# SWD_PROGRAMMER.net
KiCad netlist of a schematic drawn in EAGLE
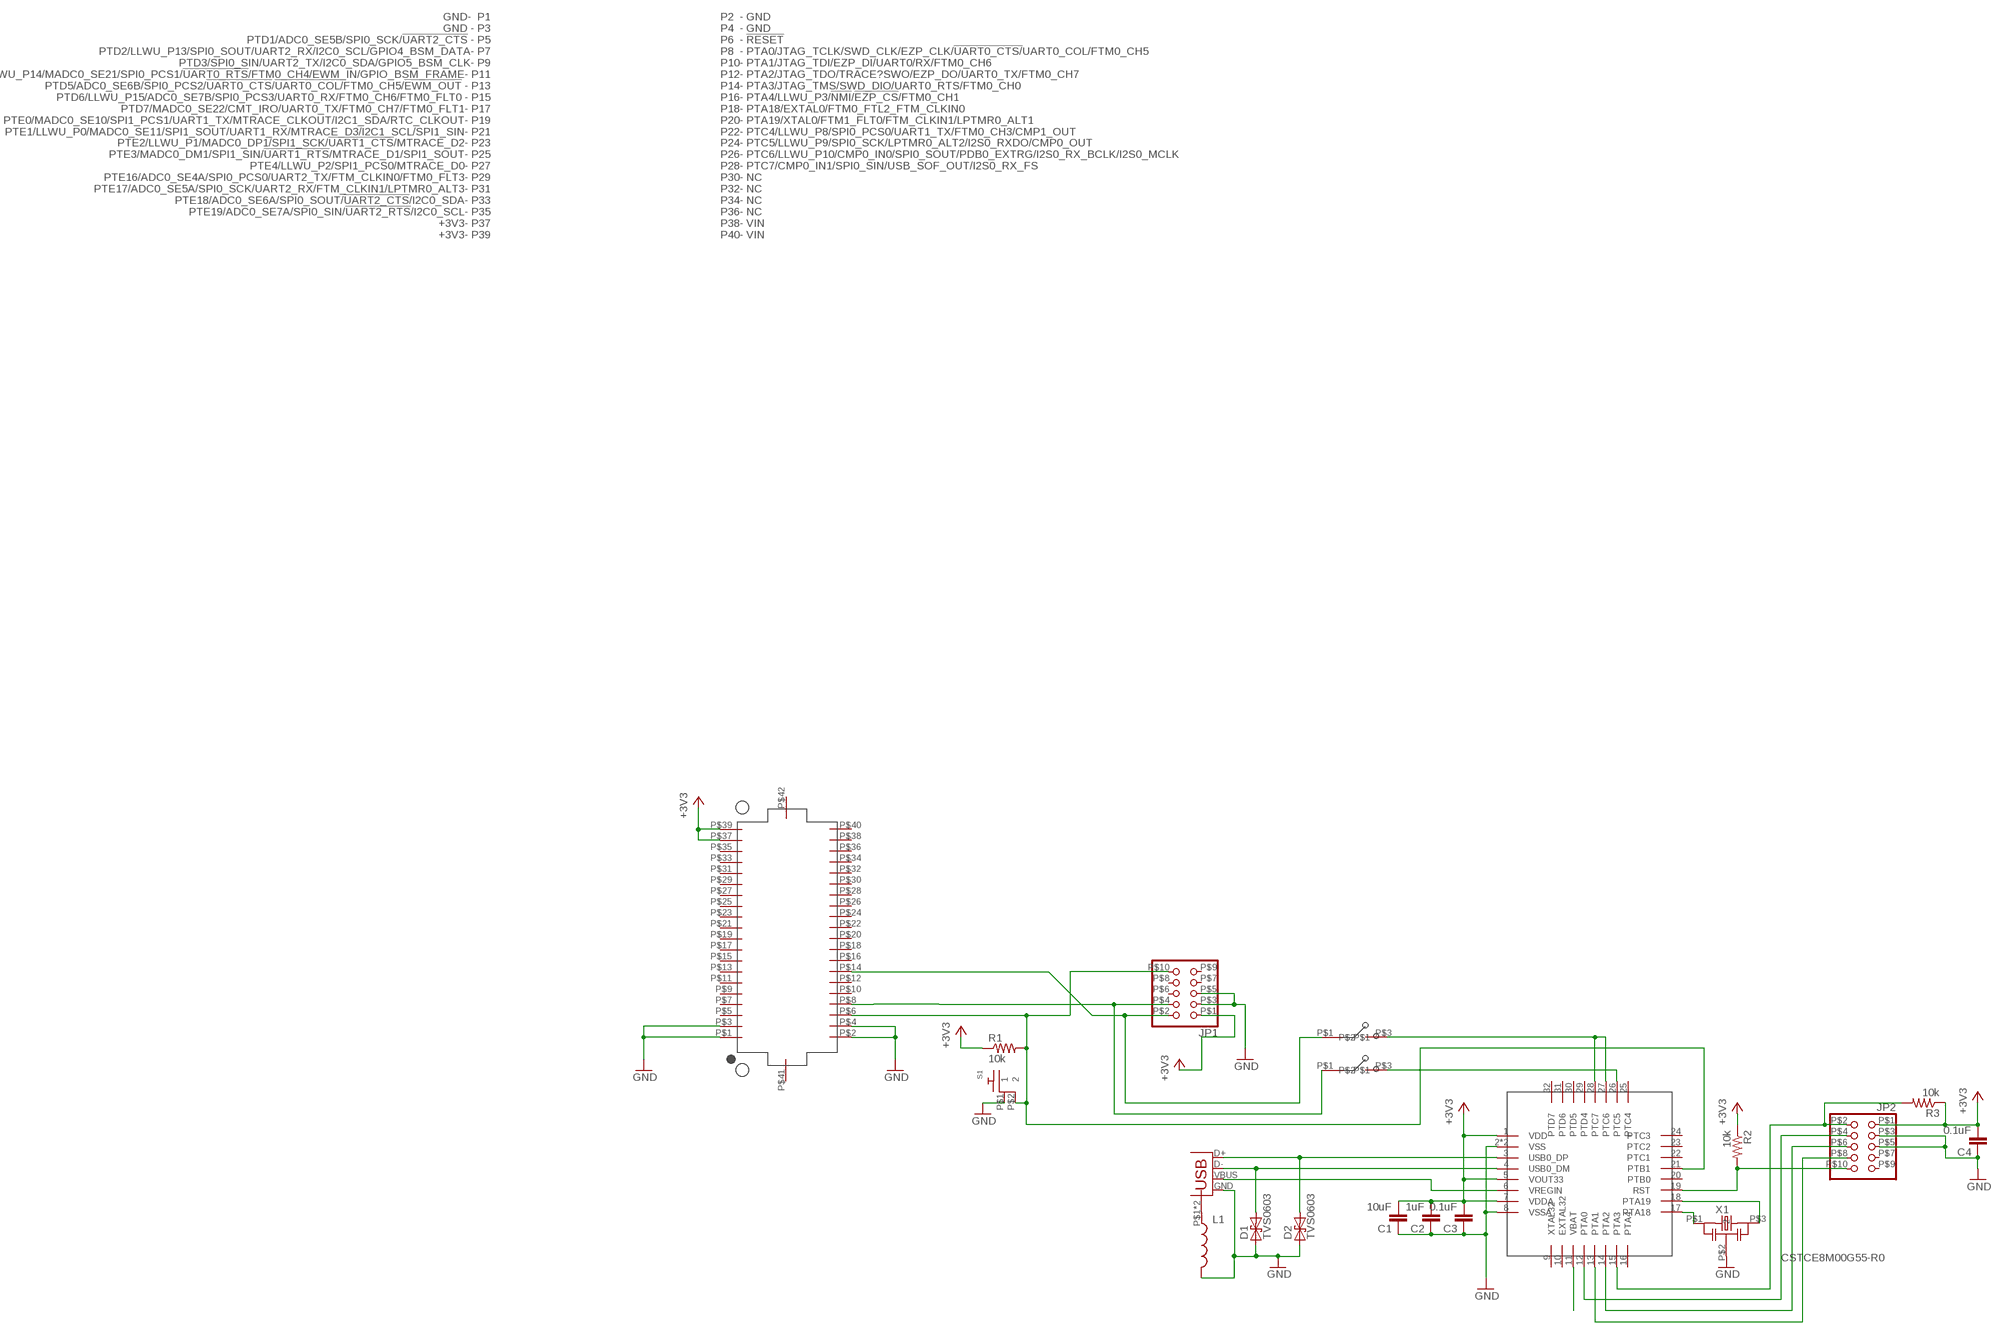
[diagram p0: schematic, sheet 1]

(export (version "E")
  (design (tool "Eeschema 10.0.6"))
  (components
    (comp (ref "C1")
      (value "10uF")
      (footprint "eagle-import:C0805")
      (libsource (lib "eagle-import") (part "RF-C0805"))
    )
    (comp (ref "C2")
      (value "1uF")
      (footprint "eagle-import:C0805")
      (libsource (lib "eagle-import") (part "RF-C0805"))
    )
    (comp (ref "C3")
      (value "0.1uF")
      (footprint "eagle-import:C0805")
      (libsource (lib "eagle-import") (part "RF-C0805"))
    )
    (comp (ref "C4")
      (value "0.1uF")
      (footprint "eagle-import:C0805")
      (libsource (lib "eagle-import") (part "RF-C0805"))
    )
    (comp (ref "D1")
      (value "TVS0603")
      (footprint "eagle-import:0603-RES")
      (libsource (lib "eagle-import") (part "TVS0603"))
    )
    (comp (ref "D2")
      (value "TVS0603")
      (footprint "eagle-import:0603-RES")
      (libsource (lib "eagle-import") (part "TVS0603"))
    )
    (comp (ref "J1")
      (value "USB_B")
      (footprint "eagle-import:USB-B-PTH-VERTICAL")
      (libsource (lib "eagle-import") (part "USB_B"))
    )
    (comp (ref "JP1")
      (value "PINHD-2X5SMALL")
      (footprint "eagle-import:2X5HDR")
      (libsource (lib "eagle-import") (part "PINHD-2X5SMALL"))
    )
    (comp (ref "JP2")
      (value "PINHD-2X5SMALL")
      (footprint "eagle-import:2X5HDR")
      (libsource (lib "eagle-import") (part "PINHD-2X5SMALL"))
    )
    (comp (ref "L1")
      (value "INDUCTOR0603")
      (footprint "eagle-import:0603")
      (libsource (lib "eagle-import") (part "INDUCTOR0603"))
    )
    (comp (ref "R1")
      (value "10k")
      (footprint "eagle-import:RF-C0805")
      (libsource (lib "eagle-import") (part "RF-R0805"))
    )
    (comp (ref "R2")
      (value "10k")
      (footprint "eagle-import:RF-C0805")
      (libsource (lib "eagle-import") (part "RF-R0805"))
    )
    (comp (ref "R3")
      (value "10k")
      (footprint "eagle-import:RF-C0805")
      (libsource (lib "eagle-import") (part "RF-R0805"))
    )
    (comp (ref "S1")
      (value "RA_BUTTON")
      (footprint "eagle-import:RA_BUTTON")
      (libsource (lib "eagle-import") (part "RA_BUTTON"))
    )
    (comp (ref "SW1")
      (value "CJS")
      (footprint "eagle-import:CJS")
      (libsource (lib "eagle-import") (part "CJS"))
    )
    (comp (ref "SW2")
      (value "CJS")
      (footprint "eagle-import:CJS")
      (libsource (lib "eagle-import") (part "CJS"))
    )
    (comp (ref "U1")
      (value "KW2_CPU_OFFSET")
      (footprint "eagle-import:BRAIN_OFFSET")
      (libsource (lib "eagle-import") (part "KW2_CPU_OFFSET"))
    )
    (comp (ref "U2")
      (value "KL20PAD")
      (footprint "eagle-import:QFN-32")
      (libsource (lib "eagle-import") (part "KL20PAD"))
    )
    (comp (ref "X1")
      (value "CSTCE8M00G55-R0")
      (footprint "eagle-import:CSTCE_G_A")
      (libsource (lib "eagle-import") (part "CSTCE8M00G55-R0"))
    )
  )
  (nets
    (net (code "1") (name "+3V3") (class "Default")
      (node (ref "C1") (pin "2") (pinfunction "2_2") (pintype "passive"))
      (node (ref "C2") (pin "2") (pinfunction "2_2") (pintype "passive"))
      (node (ref "C3") (pin "2") (pinfunction "2_2") (pintype "passive"))
      (node (ref "C4") (pin "2") (pinfunction "2_2") (pintype "passive"))
      (node (ref "JP1") (pin "P$1") (pinfunction "1_P$1") (pintype "passive"))
      (node (ref "JP2") (pin "P$1") (pinfunction "1_P$1") (pintype "passive"))
      (node (ref "R1") (pin "1") (pinfunction "1_1") (pintype "passive"))
      (node (ref "R2") (pin "1") (pinfunction "1_1") (pintype "passive"))
      (node (ref "R3") (pin "1") (pinfunction "1_1") (pintype "passive"))
      (node (ref "U1") (pin "P$37") (pinfunction "+3V3_P$37") (pintype "bidirectional"))
      (node (ref "U1") (pin "P$39") (pinfunction "+3V3_P$39") (pintype "bidirectional"))
      (node (ref "U2") (pin "1") (pinfunction "VDD_1") (pintype "bidirectional"))
      (node (ref "U2") (pin "5") (pinfunction "VOUT33_5") (pintype "bidirectional"))
      (node (ref "U2") (pin "7") (pinfunction "VDDA_7") (pintype "bidirectional"))
    )
    (net (code "2") (name "GND") (class "Default")
      (node (ref "C1") (pin "1") (pinfunction "1_1") (pintype "passive"))
      (node (ref "C2") (pin "1") (pinfunction "1_1") (pintype "passive"))
      (node (ref "C3") (pin "1") (pinfunction "1_1") (pintype "passive"))
      (node (ref "C4") (pin "1") (pinfunction "1_1") (pintype "passive"))
      (node (ref "D1") (pin "1") (pinfunction "1_1") (pintype "passive"))
      (node (ref "D2") (pin "1") (pinfunction "1_1") (pintype "passive"))
      (node (ref "J1") (pin "GND") (pinfunction "GND_GND") (pintype "bidirectional"))
      (node (ref "JP1") (pin "P$3") (pinfunction "3_P$3") (pintype "passive"))
      (node (ref "JP1") (pin "P$5") (pinfunction "5_P$5") (pintype "passive"))
      (node (ref "JP2") (pin "P$3") (pinfunction "3_P$3") (pintype "passive"))
      (node (ref "JP2") (pin "P$5") (pinfunction "5_P$5") (pintype "passive"))
      (node (ref "L1") (pin "2") (pinfunction "2_2") (pintype "passive"))
      (node (ref "S1") (pin "P$1") (pinfunction "1_P$1") (pintype "input"))
      (node (ref "U1") (pin "P$1") (pinfunction "GND_P$1") (pintype "bidirectional"))
      (node (ref "U1") (pin "P$2") (pinfunction "GND_P$2") (pintype "bidirectional"))
      (node (ref "U1") (pin "P$3") (pinfunction "GND_P$3") (pintype "bidirectional"))
      (node (ref "U1") (pin "P$4") (pinfunction "GND_P$4") (pintype "bidirectional"))
      (node (ref "U2") (pin "2") (pinfunction "VSS_2") (pintype "bidirectional"))
      (node (ref "U2") (pin "8") (pinfunction "VSSA_8") (pintype "bidirectional"))
      (node (ref "U2") (pin "EP") (pinfunction "VSS_EP") (pintype "bidirectional"))
      (node (ref "X1") (pin "P$2") (pinfunction "2_P$2") (pintype "passive"))
    )
    (net (code "3") (name "Net-(J1-SHIELD-PadP$1)") (class "Default")
      (node (ref "J1") (pin "P$1") (pinfunction "SHIELD_P$1") (pintype "bidirectional"))
      (node (ref "J1") (pin "P$2") (pinfunction "SHIELD_P$2") (pintype "bidirectional"))
      (node (ref "L1") (pin "1") (pinfunction "1_1") (pintype "passive"))
    )
    (net (code "4") (name "Net-(JP1-2)") (class "Default")
      (node (ref "JP1") (pin "P$2") (pinfunction "2_P$2") (pintype "passive"))
      (node (ref "SW1") (pin "P$1") (pinfunction "P$1_P$1") (pintype "bidirectional"))
      (node (ref "U1") (pin "P$14") (pinfunction "PTA3/JTAG_TMS/SWD_DIO/UART0_RTS/FTM0_CH0_P$14") (pintype "bidirectional"))
    )
    (net (code "5") (name "Net-(JP1-4)") (class "Default")
      (node (ref "JP1") (pin "P$4") (pinfunction "4_P$4") (pintype "passive"))
      (node (ref "SW2") (pin "P$1") (pinfunction "P$1_P$1") (pintype "bidirectional"))
      (node (ref "U1") (pin "P$8") (pinfunction "PTA0/JTAG_TCLK/SWD_CLK/EZP_CLK/~{UART0_CTS/}UART0_COL/FTM0_CH5_P$8") (pintype "bidirectional"))
    )
    (net (code "6") (name "Net-(JP1-10)") (class "Default")
      (node (ref "JP1") (pin "P$10") (pinfunction "10_P$10") (pintype "passive"))
      (node (ref "R1") (pin "2") (pinfunction "2_2") (pintype "passive"))
      (node (ref "S1") (pin "P$2") (pinfunction "2_P$2") (pintype "input"))
      (node (ref "U1") (pin "P$6") (pinfunction "~{RESET}_P$6") (pintype "bidirectional"))
      (node (ref "U2") (pin "21") (pinfunction "PTB1_21") (pintype "bidirectional"))
    )
    (net (code "7") (name "Net-(JP2-2)") (class "Default")
      (node (ref "JP2") (pin "P$2") (pinfunction "2_P$2") (pintype "passive"))
      (node (ref "R3") (pin "2") (pinfunction "2_2") (pintype "passive"))
      (node (ref "U2") (pin "15") (pinfunction "PTA3_15") (pintype "bidirectional"))
    )
    (net (code "8") (name "Net-(JP2-4)") (class "Default")
      (node (ref "JP2") (pin "P$4") (pinfunction "4_P$4") (pintype "passive"))
      (node (ref "U2") (pin "12") (pinfunction "PTA0_12") (pintype "bidirectional"))
    )
    (net (code "9") (name "Net-(JP2-6)") (class "Default")
      (node (ref "JP2") (pin "P$6") (pinfunction "6_P$6") (pintype "passive"))
      (node (ref "U2") (pin "14") (pinfunction "PTA2_14") (pintype "bidirectional"))
    )
    (net (code "10") (name "Net-(JP2-8)") (class "Default")
      (node (ref "JP2") (pin "P$8") (pinfunction "8_P$8") (pintype "passive"))
      (node (ref "U2") (pin "13") (pinfunction "PTA1_13") (pintype "bidirectional"))
    )
    (net (code "11") (name "Net-(JP2-10)") (class "Default")
      (node (ref "JP2") (pin "P$10") (pinfunction "10_P$10") (pintype "passive"))
      (node (ref "R2") (pin "2") (pinfunction "2_2") (pintype "passive"))
      (node (ref "U2") (pin "19") (pinfunction "RST_19") (pintype "bidirectional"))
    )
    (net (code "12") (name "Net-(SW1-P$2)") (class "Default")
      (node (ref "SW1") (pin "P$3") (pinfunction "P$2_P$3") (pintype "bidirectional"))
      (node (ref "U2") (pin "27") (pinfunction "PTC6_27") (pintype "bidirectional"))
      (node (ref "U2") (pin "28") (pinfunction "PTC7_28") (pintype "bidirectional"))
    )
    (net (code "13") (name "Net-(SW2-P$2)") (class "Default")
      (node (ref "SW2") (pin "P$3") (pinfunction "P$2_P$3") (pintype "bidirectional"))
      (node (ref "U2") (pin "26") (pinfunction "PTC5_26") (pintype "bidirectional"))
    )
    (net (code "14") (name "Net-(U2-PTA18)") (class "Default")
      (node (ref "U2") (pin "17") (pinfunction "PTA18_17") (pintype "bidirectional"))
      (node (ref "X1") (pin "P$1") (pinfunction "1_P$1") (pintype "passive"))
    )
    (net (code "15") (name "Net-(U2-PTA19)") (class "Default")
      (node (ref "U2") (pin "18") (pinfunction "PTA19_18") (pintype "bidirectional"))
      (node (ref "X1") (pin "P$3") (pinfunction "3_P$3") (pintype "passive"))
    )
    (net (code "16") (name "Net-(U2-USB0_DM)") (class "Default")
      (node (ref "D1") (pin "2") (pinfunction "2_2") (pintype "passive"))
      (node (ref "J1") (pin "D-") (pinfunction "D-_D-") (pintype "bidirectional"))
      (node (ref "U2") (pin "4") (pinfunction "USB0_DM_4") (pintype "bidirectional"))
    )
    (net (code "17") (name "Net-(U2-USB0_DP)") (class "Default")
      (node (ref "D2") (pin "2") (pinfunction "2_2") (pintype "passive"))
      (node (ref "J1") (pin "D+") (pinfunction "D+_D+") (pintype "bidirectional"))
      (node (ref "U2") (pin "3") (pinfunction "USB0_DP_3") (pintype "bidirectional"))
    )
    (net (code "18") (name "Net-(U2-VREGIN)") (class "Default")
      (node (ref "J1") (pin "VBUS") (pinfunction "VBUS_VBUS") (pintype "bidirectional"))
      (node (ref "U2") (pin "6") (pinfunction "VREGIN_6") (pintype "bidirectional"))
    )
    (net (code "19") (name "unconnected-(JP1-6-PadP$6)") (class "Default")
      (node (ref "JP1") (pin "P$6") (pinfunction "6_P$6") (pintype "passive"))
    )
    (net (code "20") (name "unconnected-(JP1-7-PadP$7)") (class "Default")
      (node (ref "JP1") (pin "P$7") (pinfunction "7_P$7") (pintype "passive"))
    )
    (net (code "21") (name "unconnected-(JP1-8-PadP$8)") (class "Default")
      (node (ref "JP1") (pin "P$8") (pinfunction "8_P$8") (pintype "passive"))
    )
    (net (code "22") (name "unconnected-(JP1-9-PadP$9)") (class "Default")
      (node (ref "JP1") (pin "P$9") (pinfunction "9_P$9") (pintype "passive"))
    )
    (net (code "23") (name "unconnected-(JP2-7-PadP$7)") (class "Default")
      (node (ref "JP2") (pin "P$7") (pinfunction "7_P$7") (pintype "passive"))
    )
    (net (code "24") (name "unconnected-(JP2-9-PadP$9)") (class "Default")
      (node (ref "JP2") (pin "P$9") (pinfunction "9_P$9") (pintype "passive"))
    )
    (net (code "25") (name "unconnected-(U1-NC-PadP$30)") (class "Default")
      (node (ref "U1") (pin "P$30") (pinfunction "NC_P$30") (pintype "bidirectional"))
    )
    (net (code "26") (name "unconnected-(U1-NC-PadP$32)") (class "Default")
      (node (ref "U1") (pin "P$32") (pinfunction "NC_P$32") (pintype "bidirectional"))
    )
    (net (code "27") (name "unconnected-(U1-NC-PadP$34)") (class "Default")
      (node (ref "U1") (pin "P$34") (pinfunction "NC_P$34") (pintype "bidirectional"))
    )
    (net (code "28") (name "unconnected-(U1-NC-PadP$36)") (class "Default")
      (node (ref "U1") (pin "P$36") (pinfunction "NC_P$36") (pintype "bidirectional"))
    )
    (net (code "29") (name "unconnected-(U1-PTA1{slash}JTAG_TDI{slash}EZP_DI{slash}UART0{slash}RX{slash}FTM0_CH6-PadP$10)") (class "Default")
      (node (ref "U1") (pin "P$10") (pinfunction "PTA1/JTAG_TDI/EZP_DI/UART0/RX/FTM0_CH6_P$10") (pintype "bidirectional"))
    )
    (net (code "30") (name "unconnected-(U1-PTA2{slash}JTAG_TDO{slash}TRACE?SWO{slash}EZP_DO{slash}UART0_TX{slash}FTM0_CH7-PadP$12)") (class "Default")
      (node (ref "U1") (pin "P$12") (pinfunction "PTA2/JTAG_TDO/TRACE?SWO/EZP_DO/UART0_TX/FTM0_CH7_P$12") (pintype "bidirectional"))
    )
    (net (code "31") (name "unconnected-(U1-PTA4{slash}LLWU_P3{slash}~{NMI}{slash}~{EZP_CS}{slash}FTM0_CH1-PadP$16)") (class "Default")
      (node (ref "U1") (pin "P$16") (pinfunction "PTA4/LLWU_P3/~{NMI}/~{EZP_CS}/FTM0_CH1_P$16") (pintype "bidirectional"))
    )
    (net (code "32") (name "unconnected-(U1-PTA18{slash}EXTAL0{slash}FTM0_FTL2_FTM_CLKIN0-PadP$18)") (class "Default")
      (node (ref "U1") (pin "P$18") (pinfunction "PTA18/EXTAL0/FTM0_FTL2_FTM_CLKIN0_P$18") (pintype "bidirectional"))
    )
    (net (code "33") (name "unconnected-(U1-PTA19{slash}XTAL0{slash}FTM1_FLT0{slash}FTM_CLKIN1{slash}LPTMR0_ALT1-PadP$20)") (class "Default")
      (node (ref "U1") (pin "P$20") (pinfunction "PTA19/XTAL0/FTM1_FLT0/FTM_CLKIN1/LPTMR0_ALT1_P$20") (pintype "bidirectional"))
    )
    (net (code "34") (name "unconnected-(U1-PTC4{slash}LLWU_P8{slash}SPI0_PCS0{slash}UART1_TX{slash}FTM0_CH3{slash}CMP1_OUT-PadP$22)") (class "Default")
      (node (ref "U1") (pin "P$22") (pinfunction "PTC4/LLWU_P8/SPI0_PCS0/UART1_TX/FTM0_CH3/CMP1_OUT_P$22") (pintype "bidirectional"))
    )
    (net (code "35") (name "unconnected-(U1-PTC5{slash}LLWU_P8{slash}SPI0_PCS0{slash}UART1_TX{slash}FTM0_CH3{slash}CMP1_OUT-PadP$24)") (class "Default")
      (node (ref "U1") (pin "P$24") (pinfunction "PTC5/LLWU_P8/SPI0_PCS0/UART1_TX/FTM0_CH3/CMP1_OUT_P$24") (pintype "bidirectional"))
    )
    (net (code "36") (name "unconnected-(U1-PTC6{slash}LLWU_P10{slash}CMP0_IN0{slash}SPI0_SOUT{slash}PDB0_EXTRG{slash}I2S0_RX_BCLK{slash}I2S0_MCLK-PadP$26)") (class "Default")
      (node (ref "U1") (pin "P$26") (pinfunction "PTC6/LLWU_P10/CMP0_IN0/SPI0_SOUT/PDB0_EXTRG/I2S0_RX_BCLK/I2S0_MCLK_P$26") (pintype "bidirectional"))
    )
    (net (code "37") (name "unconnected-(U1-PTC7{slash}CMP0_IN1{slash}SPI0_SIN{slash}USB_SOF_OUT{slash}I2S0_RX_FS-PadP$28)") (class "Default")
      (node (ref "U1") (pin "P$28") (pinfunction "PTC7/CMP0_IN1/SPI0_SIN/USB_SOF_OUT/I2S0_RX_FS_P$28") (pintype "bidirectional"))
    )
    (net (code "38") (name "unconnected-(U1-PTD1{slash}ADC0_SE5B{slash}SPI0_SCK{slash}~{UART2_CTS}-PadP$5)") (class "Default")
      (node (ref "U1") (pin "P$5") (pinfunction "PTD1/ADC0_SE5B/SPI0_SCK/~{UART2_CTS}_P$5") (pintype "bidirectional"))
    )
    (net (code "39") (name "unconnected-(U1-PTD2{slash}LLWU_P13{slash}SPI0_SOUT{slash}UART2_RX{slash}I2C0_SCL{slash}GPIO4_BSM_DATA-PadP$7)") (class "Default")
      (node (ref "U1") (pin "P$7") (pinfunction "PTD2/LLWU_P13/SPI0_SOUT/UART2_RX/I2C0_SCL/GPIO4_BSM_DATA_P$7") (pintype "bidirectional"))
    )
    (net (code "40") (name "unconnected-(U1-PTD3{slash}SPI0_SIN{slash}UART2_TX{slash}I2C0_SDA{slash}GPIO5_BSM_CLK-PadP$9)") (class "Default")
      (node (ref "U1") (pin "P$9") (pinfunction "PTD3/SPI0_SIN/UART2_TX/I2C0_SDA/GPIO5_BSM_CLK_P$9") (pintype "bidirectional"))
    )
    (net (code "41") (name "unconnected-(U1-PTD4{slash}LLWU_P14{slash}MADC0_SE21{slash}SPI0_PCS1{slash}~{UART0_RTS}{slash}FTM0_CH4{slash}EWM_IN{slash}GPIO_BSM_FRAME-PadP$11)") (class "Default")
      (node (ref "U1") (pin "P$11") (pinfunction "PTD4/LLWU_P14/MADC0_SE21/SPI0_PCS1/~{UART0_RTS}/FTM0_CH4/EWM_IN/GPIO_BSM_FRAME_P$11") (pintype "bidirectional"))
    )
    (net (code "42") (name "unconnected-(U1-PTD5{slash}ADC0_SE6B{slash}SPI0_PCS2{slash}~{UART0_CTS}{slash}~{UART0_COL}{slash}FTM0_CH5{slash}~{EWM_OUT}-PadP$13)") (class "Default")
      (node (ref "U1") (pin "P$13") (pinfunction "PTD5/ADC0_SE6B/SPI0_PCS2/~{UART0_CTS}/~{UART0_COL}/FTM0_CH5/~{EWM_OUT}_P$13") (pintype "bidirectional"))
    )
    (net (code "43") (name "unconnected-(U1-PTD6{slash}LLWU_P15{slash}ADC0_SE7B{slash}SPI0_PCS3{slash}UART0_RX{slash}FTM0_CH6{slash}FTM0_FLT0-PadP$15)") (class "Default")
      (node (ref "U1") (pin "P$15") (pinfunction "PTD6/LLWU_P15/ADC0_SE7B/SPI0_PCS3/UART0_RX/FTM0_CH6/FTM0_FLT0_P$15") (pintype "bidirectional"))
    )
    (net (code "44") (name "unconnected-(U1-PTD7{slash}MADC0_SE22{slash}CMT_IRO{slash}UART0_TX{slash}FTM0_CH7{slash}FTM0_FLT1-PadP$17)") (class "Default")
      (node (ref "U1") (pin "P$17") (pinfunction "PTD7/MADC0_SE22/CMT_IRO/UART0_TX/FTM0_CH7/FTM0_FLT1_P$17") (pintype "bidirectional"))
    )
    (net (code "45") (name "unconnected-(U1-PTE0{slash}MADC0_SE10{slash}SPI1_PCS1{slash}UART1_TX{slash}MTRACE_CLKOUT{slash}I2C1_SDA{slash}RTC_CLKOUT-PadP$19)") (class "Default")
      (node (ref "U1") (pin "P$19") (pinfunction "PTE0/MADC0_SE10/SPI1_PCS1/UART1_TX/MTRACE_CLKOUT/I2C1_SDA/RTC_CLKOUT_P$19") (pintype "bidirectional"))
    )
    (net (code "46") (name "unconnected-(U1-PTE1{slash}LLWU_P0{slash}MADC0_SE11{slash}SPI1_SOUT{slash}UART1_RX{slash}MTRACE_D3{slash}I2C1_SCL{slash}SPI1_SIN-PadP$21)") (class "Default")
      (node (ref "U1") (pin "P$21") (pinfunction "PTE1/LLWU_P0/MADC0_SE11/SPI1_SOUT/UART1_RX/MTRACE_D3/I2C1_SCL/SPI1_SIN_P$21") (pintype "bidirectional"))
    )
    (net (code "47") (name "unconnected-(U1-PTE2{slash}LLWU_P1{slash}MADC0_DP1{slash}SPI1_SCK{slash}~{UART1_CTS}{slash}MTRACE_D2-PadP$23)") (class "Default")
      (node (ref "U1") (pin "P$23") (pinfunction "PTE2/LLWU_P1/MADC0_DP1/SPI1_SCK/~{UART1_CTS}/MTRACE_D2_P$23") (pintype "bidirectional"))
    )
    (net (code "48") (name "unconnected-(U1-PTE3{slash}MADC0_DM1{slash}SPI1_SIN{slash}~{UART1_RTS}{slash}MTRACE_D1{slash}SPI1_SOUT-PadP$25)") (class "Default")
      (node (ref "U1") (pin "P$25") (pinfunction "PTE3/MADC0_DM1/SPI1_SIN/~{UART1_RTS}/MTRACE_D1/SPI1_SOUT_P$25") (pintype "bidirectional"))
    )
    (net (code "49") (name "unconnected-(U1-PTE4{slash}LLWU_P2{slash}SPI1_PCS0{slash}MTRACE_D0-PadP$27)") (class "Default")
      (node (ref "U1") (pin "P$27") (pinfunction "PTE4/LLWU_P2/SPI1_PCS0/MTRACE_D0_P$27") (pintype "bidirectional"))
    )
    (net (code "50") (name "unconnected-(U1-PTE16{slash}ADC0_SE4A{slash}SPI0_PCS0{slash}UART2_TX{slash}FTM_CLKIN0{slash}FTM0_FLT3-PadP$29)") (class "Default")
      (node (ref "U1") (pin "P$29") (pinfunction "PTE16/ADC0_SE4A/SPI0_PCS0/UART2_TX/FTM_CLKIN0/FTM0_FLT3_P$29") (pintype "bidirectional"))
    )
    (net (code "51") (name "unconnected-(U1-PTE17{slash}ADC0_SE5A{slash}SPI0_SCK{slash}UART2_RX{slash}FTM_CLKIN1{slash}LPTMR0_ALT3-PadP$31)") (class "Default")
      (node (ref "U1") (pin "P$31") (pinfunction "PTE17/ADC0_SE5A/SPI0_SCK/UART2_RX/FTM_CLKIN1/LPTMR0_ALT3_P$31") (pintype "bidirectional"))
    )
    (net (code "52") (name "unconnected-(U1-PTE18{slash}ADC0_SE6A{slash}SPI0_SOUT{slash}~{UART2_CTS}{slash}I2C0_SDA-PadP$33)") (class "Default")
      (node (ref "U1") (pin "P$33") (pinfunction "PTE18/ADC0_SE6A/SPI0_SOUT/~{UART2_CTS}/I2C0_SDA_P$33") (pintype "bidirectional"))
    )
    (net (code "53") (name "unconnected-(U1-PTE19{slash}ADC0_SE7A{slash}SPI0_SIN{slash}~{UART2_RTS}{slash}I2C0_SCL-PadP$35)") (class "Default")
      (node (ref "U1") (pin "P$35") (pinfunction "PTE19/ADC0_SE7A/SPI0_SIN/~{UART2_RTS}/I2C0_SCL_P$35") (pintype "bidirectional"))
    )
    (net (code "54") (name "unconnected-(U1-PadP$41)") (class "Default")
      (node (ref "U1") (pin "P$41") (pinfunction "P$41_P$41") (pintype "bidirectional"))
    )
    (net (code "55") (name "unconnected-(U1-PadP$42)") (class "Default")
      (node (ref "U1") (pin "P$42") (pinfunction "P$42_P$42") (pintype "bidirectional"))
    )
    (net (code "56") (name "unconnected-(U1-VIN-PadP$38)") (class "Default")
      (node (ref "U1") (pin "P$38") (pinfunction "VIN_P$38") (pintype "bidirectional"))
    )
    (net (code "57") (name "unconnected-(U1-VIN-PadP$40)") (class "Default")
      (node (ref "U1") (pin "P$40") (pinfunction "VIN_P$40") (pintype "bidirectional"))
    )
    (net (code "58") (name "unconnected-(U2-EXTAL32-Pad10)") (class "Default")
      (node (ref "U2") (pin "10") (pinfunction "EXTAL32_10") (pintype "bidirectional"))
    )
    (net (code "59") (name "unconnected-(U2-PTA4-Pad16)") (class "Default")
      (node (ref "U2") (pin "16") (pinfunction "PTA4_16") (pintype "bidirectional"))
    )
    (net (code "60") (name "unconnected-(U2-PTB0-Pad20)") (class "Default")
      (node (ref "U2") (pin "20") (pinfunction "PTB0_20") (pintype "bidirectional"))
    )
    (net (code "61") (name "unconnected-(U2-PTC1-Pad22)") (class "Default")
      (node (ref "U2") (pin "22") (pinfunction "PTC1_22") (pintype "bidirectional"))
    )
    (net (code "62") (name "unconnected-(U2-PTC2-Pad23)") (class "Default")
      (node (ref "U2") (pin "23") (pinfunction "PTC2_23") (pintype "bidirectional"))
    )
    (net (code "63") (name "unconnected-(U2-PTC3-Pad24)") (class "Default")
      (node (ref "U2") (pin "24") (pinfunction "PTC3_24") (pintype "bidirectional"))
    )
    (net (code "64") (name "unconnected-(U2-PTC4-Pad25)") (class "Default")
      (node (ref "U2") (pin "25") (pinfunction "PTC4_25") (pintype "bidirectional"))
    )
    (net (code "65") (name "unconnected-(U2-PTD4-Pad29)") (class "Default")
      (node (ref "U2") (pin "29") (pinfunction "PTD4_29") (pintype "bidirectional"))
    )
    (net (code "66") (name "unconnected-(U2-PTD5-Pad30)") (class "Default")
      (node (ref "U2") (pin "30") (pinfunction "PTD5_30") (pintype "bidirectional"))
    )
    (net (code "67") (name "unconnected-(U2-PTD6-Pad31)") (class "Default")
      (node (ref "U2") (pin "31") (pinfunction "PTD6_31") (pintype "bidirectional"))
    )
    (net (code "68") (name "unconnected-(U2-PTD7-Pad32)") (class "Default")
      (node (ref "U2") (pin "32") (pinfunction "PTD7_32") (pintype "bidirectional"))
    )
    (net (code "69") (name "unconnected-(U2-VBAT-Pad11)") (class "Default")
      (node (ref "U2") (pin "11") (pinfunction "VBAT_11") (pintype "bidirectional"))
    )
    (net (code "70") (name "unconnected-(U2-XTAL32-Pad9)") (class "Default")
      (node (ref "U2") (pin "9") (pinfunction "XTAL32_9") (pintype "bidirectional"))
    )
  )
)
